# hawb-hat.net
KiCad netlist of a schematic drawn in EAGLE
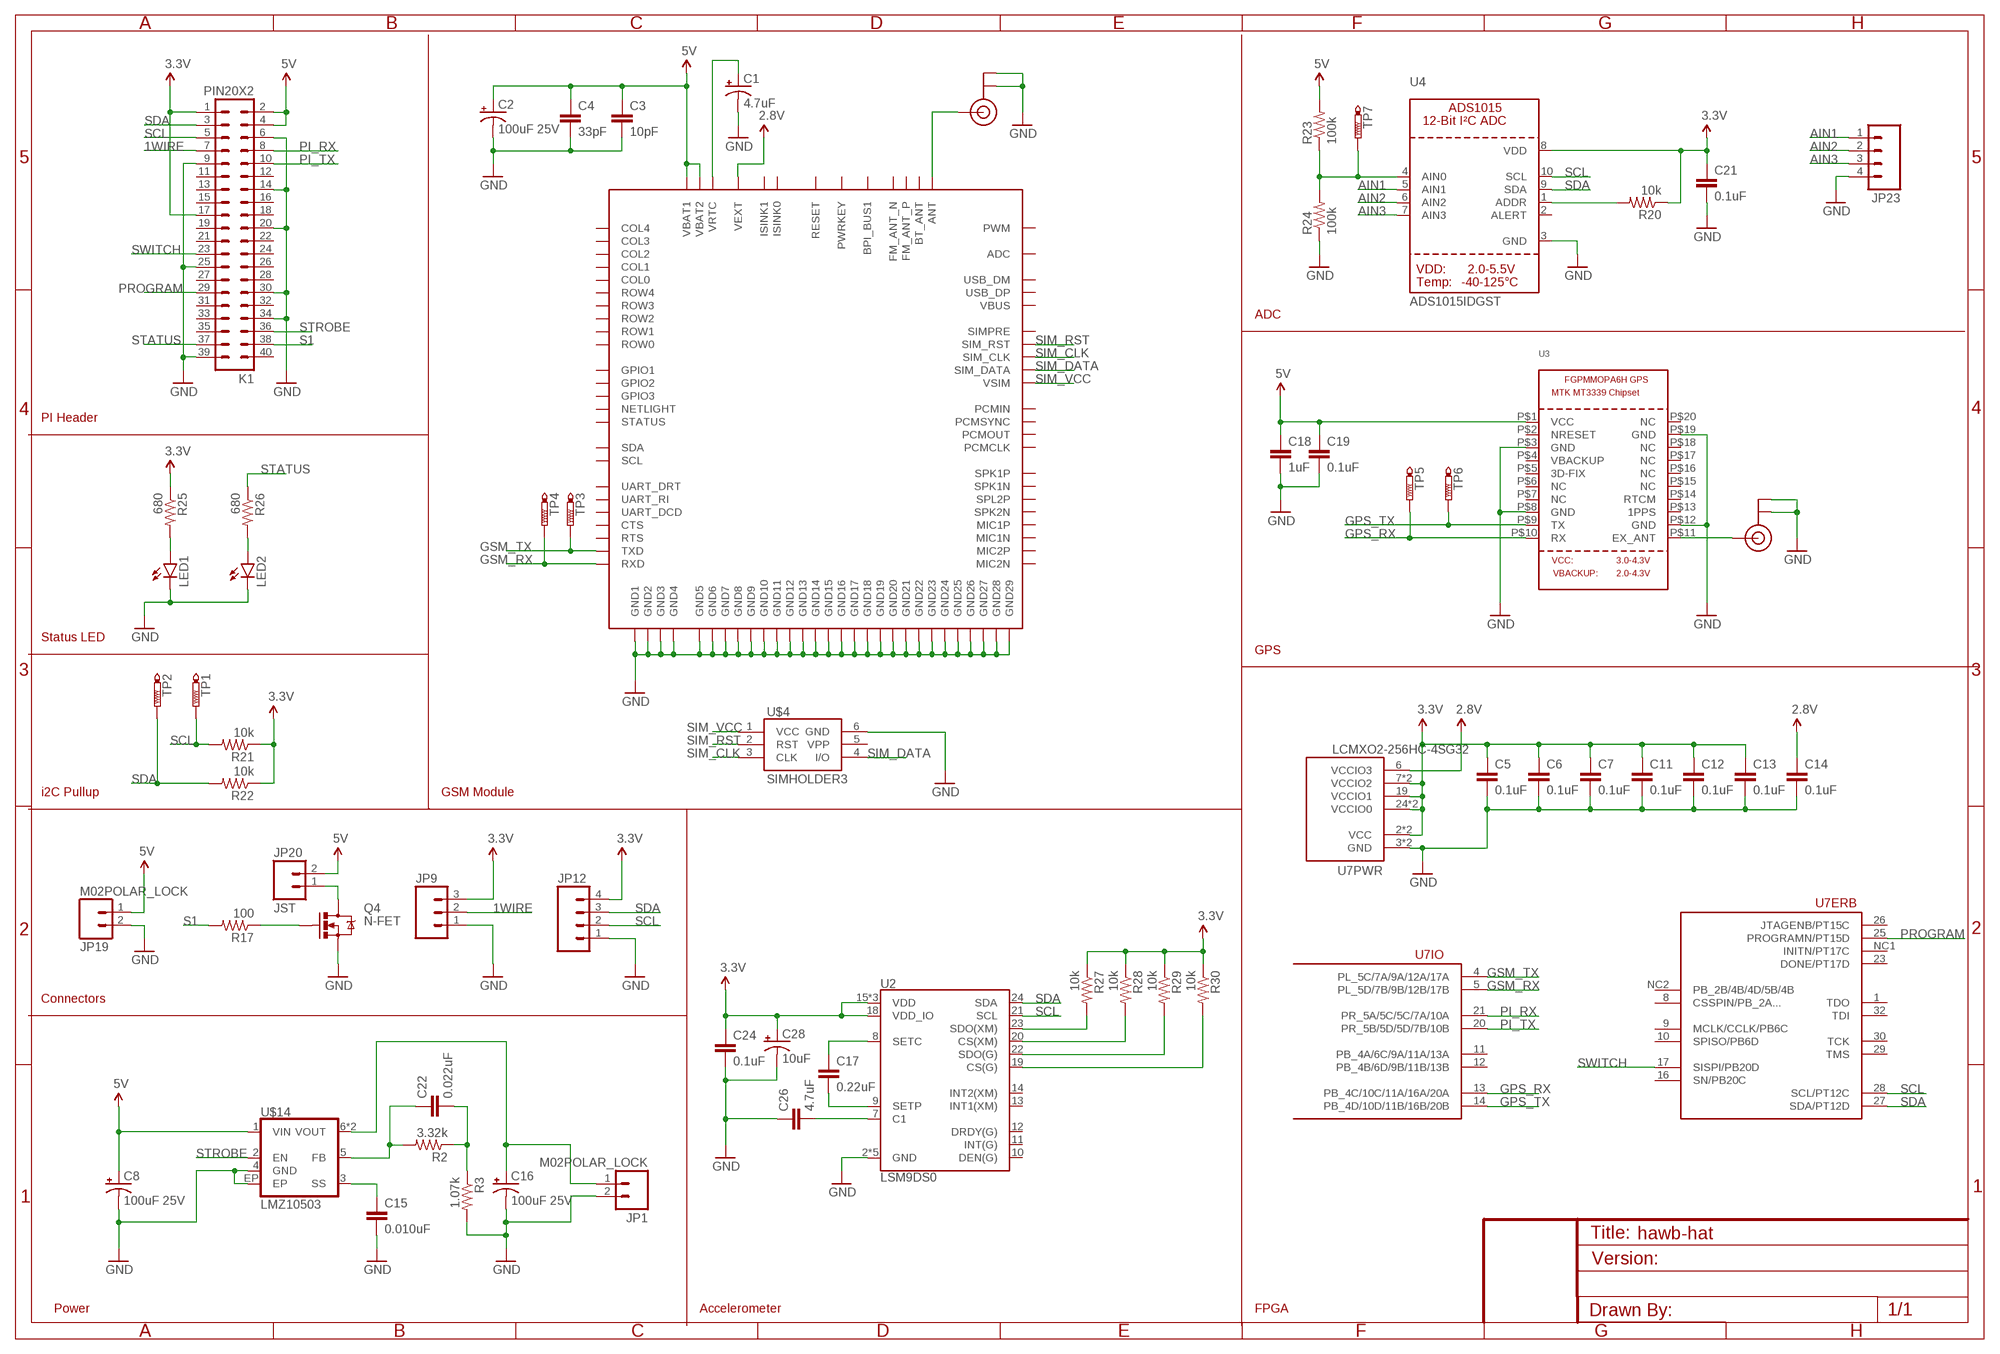
[diagram p0: schematic, sheet 1]

(export (version "E")
  (design (tool "Eeschema 10.0.6"))
  (components
    (comp (ref "C1")
      (value "4.7uF")
      (footprint "eagle-import:EIA3216-KIT")
      (libsource (lib "eagle-import") (part "sparkfun_CAP_POL1206-KIT"))
    )
    (comp (ref "C2")
      (value "100uF 25V")
      (footprint "eagle-import:NIPPON_F80")
      (libsource (lib "eagle-import") (part "CAP_POLF80"))
    )
    (comp (ref "C3")
      (value "10pF")
      (footprint "eagle-import:C0603")
      (libsource (lib "eagle-import") (part "C-EUC0603"))
    )
    (comp (ref "C4")
      (value "33pF")
      (footprint "eagle-import:C0603")
      (libsource (lib "eagle-import") (part "C-EUC0603"))
    )
    (comp (ref "C5")
      (value "0.1uF")
      (footprint "eagle-import:C0603")
      (libsource (lib "eagle-import") (part "C-EUC0603"))
    )
    (comp (ref "C6")
      (value "0.1uF")
      (footprint "eagle-import:C0603")
      (libsource (lib "eagle-import") (part "C-EUC0603"))
    )
    (comp (ref "C7")
      (value "0.1uF")
      (footprint "eagle-import:C0603")
      (libsource (lib "eagle-import") (part "C-EUC0603"))
    )
    (comp (ref "C8")
      (value "100uF 25V")
      (footprint "eagle-import:NIPPON_F80")
      (libsource (lib "eagle-import") (part "CAP_POLF80"))
    )
    (comp (ref "C11")
      (value "0.1uF")
      (footprint "eagle-import:C0603")
      (libsource (lib "eagle-import") (part "C-EUC0603"))
    )
    (comp (ref "C12")
      (value "0.1uF")
      (footprint "eagle-import:C0603")
      (libsource (lib "eagle-import") (part "C-EUC0603"))
    )
    (comp (ref "C13")
      (value "0.1uF")
      (footprint "eagle-import:C0603")
      (libsource (lib "eagle-import") (part "C-EUC0603"))
    )
    (comp (ref "C14")
      (value "0.1uF")
      (footprint "eagle-import:C0603")
      (libsource (lib "eagle-import") (part "C-EUC0603"))
    )
    (comp (ref "C15")
      (value "0.010uF")
      (footprint "eagle-import:C0603")
      (libsource (lib "eagle-import") (part "C-EUC0603"))
    )
    (comp (ref "C16")
      (value "100uF 25V")
      (footprint "eagle-import:NIPPON_F80")
      (libsource (lib "eagle-import") (part "CAP_POLF80"))
    )
    (comp (ref "C17")
      (value "0.22uF")
      (footprint "eagle-import:0603-CAP")
      (libsource (lib "eagle-import") (part "CAP0603-CAP"))
    )
    (comp (ref "C18")
      (value "1uF")
      (footprint "eagle-import:C0603")
      (libsource (lib "eagle-import") (part "C-EUC0603"))
    )
    (comp (ref "C19")
      (value "0.1uF")
      (footprint "eagle-import:C0603")
      (libsource (lib "eagle-import") (part "C-EUC0603"))
    )
    (comp (ref "C21")
      (value "0.1uF")
      (footprint "eagle-import:C0603")
      (libsource (lib "eagle-import") (part "C-EUC0603"))
    )
    (comp (ref "C22")
      (value "0.022uF")
      (footprint "eagle-import:C0603")
      (libsource (lib "eagle-import") (part "C-EUC0603"))
    )
    (comp (ref "C24")
      (value "0.1uF")
      (footprint "eagle-import:0603-CAP")
      (libsource (lib "eagle-import") (part "CAP0603-CAP"))
    )
    (comp (ref "C26")
      (value "4.7uF")
      (footprint "eagle-import:0603-CAP")
      (libsource (lib "eagle-import") (part "CAP0603-CAP"))
    )
    (comp (ref "C28")
      (value "10uF")
      (footprint "eagle-import:EIA3216")
      (libsource (lib "eagle-import") (part "sparkfun_CAP_POL1206"))
    )
    (comp (ref "JP1")
      (value "M02POLAR_LOCK")
      (footprint "eagle-import:MOLEX-1X2_LOCK")
      (libsource (lib "eagle-import") (part "M02POLAR_LOCK"))
    )
    (comp (ref "JP9")
      (value "M03JST-PTH-VERT")
      (footprint "eagle-import:JST-3-PTH-VERT")
      (libsource (lib "eagle-import") (part "M03JST-PTH-VERT"))
    )
    (comp (ref "JP12")
      (value "M04JST-PTH-VERT")
      (footprint "eagle-import:JST-4-PTH-VERT")
      (libsource (lib "eagle-import") (part "M04JST-PTH-VERT"))
    )
    (comp (ref "JP19")
      (value "M02POLAR_LOCK")
      (footprint "eagle-import:MOLEX-1X2_LOCK")
      (libsource (lib "eagle-import") (part "M02POLAR_LOCK"))
    )
    (comp (ref "JP20")
      (value "JST")
      (footprint "eagle-import:JST-2-PTH-VERT")
      (libsource (lib "eagle-import") (part "M02JST-PTH-VERT"))
    )
    (comp (ref "JP23")
      (value "M04JST-PTH-VERT")
      (footprint "eagle-import:JST-4-PTH-VERT")
      (libsource (lib "eagle-import") (part "M04JST-PTH-VERT"))
    )
    (comp (ref "K1")
      (value "PIN20X2")
      (footprint "eagle-import:PIN_20X2")
      (libsource (lib "eagle-import") (part "PIN20X2"))
    )
    (comp (ref "LED1")
      (value "LED1206")
      (footprint "eagle-import:LED-1206")
      (libsource (lib "eagle-import") (part "LED1206"))
    )
    (comp (ref "LED2")
      (value "LED1206")
      (footprint "eagle-import:LED-1206")
      (libsource (lib "eagle-import") (part "LED1206"))
    )
    (comp (ref "Q4")
      (value "N-FET")
      (footprint "eagle-import:SOT23-3")
      (libsource (lib "eagle-import") (part "MOSFET-NCHANNELSMD"))
    )
    (comp (ref "R2")
      (value "3.32k")
      (footprint "eagle-import:0603-RES")
      (libsource (lib "eagle-import") (part "RESISTOR0603-RES"))
    )
    (comp (ref "R3")
      (value "1.07k")
      (footprint "eagle-import:0603-RES")
      (libsource (lib "eagle-import") (part "RESISTOR0603-RES"))
    )
    (comp (ref "R17")
      (value "100")
      (footprint "eagle-import:0603-RES")
      (libsource (lib "eagle-import") (part "RESISTOR0603-RES"))
    )
    (comp (ref "R20")
      (value "10k")
      (footprint "eagle-import:0603-RES")
      (libsource (lib "eagle-import") (part "RESISTOR0603-RES"))
    )
    (comp (ref "R21")
      (value "10k")
      (footprint "eagle-import:0603-RES")
      (libsource (lib "eagle-import") (part "RESISTOR0603-RES"))
    )
    (comp (ref "R22")
      (value "10k")
      (footprint "eagle-import:0603-RES")
      (libsource (lib "eagle-import") (part "RESISTOR0603-RES"))
    )
    (comp (ref "R23")
      (value "100k")
      (footprint "eagle-import:0603-RES")
      (libsource (lib "eagle-import") (part "RESISTOR0603-RES"))
    )
    (comp (ref "R24")
      (value "100k")
      (footprint "eagle-import:0603-RES")
      (libsource (lib "eagle-import") (part "RESISTOR0603-RES"))
    )
    (comp (ref "R25")
      (value "680")
      (footprint "eagle-import:0603-RES")
      (libsource (lib "eagle-import") (part "RESISTOR0603-RES"))
    )
    (comp (ref "R26")
      (value "680")
      (footprint "eagle-import:0603-RES")
      (libsource (lib "eagle-import") (part "RESISTOR0603-RES"))
    )
    (comp (ref "R27")
      (value "10k")
      (footprint "eagle-import:0603-RES")
      (libsource (lib "eagle-import") (part "RESISTOR0603-RES"))
    )
    (comp (ref "R28")
      (value "10k")
      (footprint "eagle-import:0603-RES")
      (libsource (lib "eagle-import") (part "RESISTOR0603-RES"))
    )
    (comp (ref "R29")
      (value "10k")
      (footprint "eagle-import:0603-RES")
      (libsource (lib "eagle-import") (part "RESISTOR0603-RES"))
    )
    (comp (ref "R30")
      (value "10k")
      (footprint "eagle-import:0603-RES")
      (libsource (lib "eagle-import") (part "RESISTOR0603-RES"))
    )
    (comp (ref "TP1")
      (value "PTR1PAD1-13")
      (footprint "eagle-import:P1-13")
      (libsource (lib "eagle-import") (part "PTR1PAD1-13"))
    )
    (comp (ref "TP2")
      (value "PTR1PAD1-13")
      (footprint "eagle-import:P1-13")
      (libsource (lib "eagle-import") (part "PTR1PAD1-13"))
    )
    (comp (ref "TP3")
      (value "PTR1PAD1-13")
      (footprint "eagle-import:P1-13")
      (libsource (lib "eagle-import") (part "PTR1PAD1-13"))
    )
    (comp (ref "TP4")
      (value "PTR1PAD1-13")
      (footprint "eagle-import:P1-13")
      (libsource (lib "eagle-import") (part "PTR1PAD1-13"))
    )
    (comp (ref "TP5")
      (value "PTR1PAD1-13")
      (footprint "eagle-import:P1-13")
      (libsource (lib "eagle-import") (part "PTR1PAD1-13"))
    )
    (comp (ref "TP6")
      (value "PTR1PAD1-13")
      (footprint "eagle-import:P1-13")
      (libsource (lib "eagle-import") (part "PTR1PAD1-13"))
    )
    (comp (ref "TP7")
      (value "PTR1PAD1-13")
      (footprint "eagle-import:P1-13")
      (libsource (lib "eagle-import") (part "PTR1PAD1-13"))
    )
    (comp (ref "U$1")
      (value "U.FL")
      (footprint "eagle-import:U.FL")
      (libsource (lib "eagle-import") (part "U.FL"))
    )
    (comp (ref "U$2")
      (value "U.FL")
      (footprint "eagle-import:U.FL")
      (libsource (lib "eagle-import") (part "U.FL"))
    )
    (comp (ref "U$4")
      (value "SIMHOLDER3")
      (footprint "eagle-import:SIMHOLDER3")
      (libsource (lib "eagle-import") (part "SIMHOLDER3"))
    )
    (comp (ref "U$5")
      (value "SIM800H")
      (footprint "eagle-import:SIM800")
      (libsource (lib "eagle-import") (part "SIM800H"))
    )
    (comp (ref "U$14")
      (value "LMZ10503")
      (footprint "eagle-import:TO-PMOD-7")
      (libsource (lib "eagle-import") (part "LMZ10503"))
    )
    (comp (ref "U2")
      (value "LSM9DS0")
      (footprint "eagle-import:LGA-24")
      (libsource (lib "eagle-import") (part "LSM9DS0"))
    )
    (comp (ref "U3")
      (value "GPS_FGPMMOPA6H")
      (footprint "eagle-import:FGPMMOPA6H")
      (libsource (lib "eagle-import") (part "GPS_FGPMMOPA6H"))
    )
    (comp (ref "U4")
      (value "ADS1015IDGST")
      (footprint "eagle-import:MSOP10")
      (libsource (lib "eagle-import") (part "ADC_ADS1015"))
    )
    (comp (ref "U7")
      (value "LCMXO2-256HC-4SG32")
      (footprint "eagle-import:QFN-32")
      (libsource (lib "eagle-import") (part "LCMXO2-256SG32HC-4"))
    )
  )
  (nets
    (net (code "1") (name "/1WIRE") (class "Default")
      (node (ref "JP9") (pin "2") (pinfunction "2_2") (pintype "passive"))
      (node (ref "K1") (pin "7") (pinfunction "7_7") (pintype "passive"))
    )
    (net (code "2") (name "/AIN1") (class "Default")
      (node (ref "JP23") (pin "1") (pinfunction "1_1") (pintype "passive"))
      (node (ref "U4") (pin "5") (pinfunction "AIN1_5") (pintype "bidirectional"))
    )
    (net (code "3") (name "/AIN2") (class "Default")
      (node (ref "JP23") (pin "2") (pinfunction "2_2") (pintype "passive"))
      (node (ref "U4") (pin "6") (pinfunction "AIN2_6") (pintype "bidirectional"))
    )
    (net (code "4") (name "/AIN3") (class "Default")
      (node (ref "JP23") (pin "3") (pinfunction "3_3") (pintype "passive"))
      (node (ref "U4") (pin "7") (pinfunction "AIN3_7") (pintype "bidirectional"))
    )
    (net (code "5") (name "/GPS_RX") (class "Default")
      (node (ref "TP5") (pin "TP") (pinfunction "TP_TP") (pintype "input"))
      (node (ref "U3") (pin "P$10") (pinfunction "RX_P$10") (pintype "bidirectional"))
      (node (ref "U7") (pin "13") (pinfunction "PB_4C/10C/11A/16A/20A_13") (pintype "bidirectional"))
    )
    (net (code "6") (name "/GPS_TX") (class "Default")
      (node (ref "TP6") (pin "TP") (pinfunction "TP_TP") (pintype "input"))
      (node (ref "U3") (pin "P$9") (pinfunction "TX_P$9") (pintype "bidirectional"))
      (node (ref "U7") (pin "14") (pinfunction "PB_4D/10D/11B/16B/20B_14") (pintype "bidirectional"))
    )
    (net (code "7") (name "/GSM_RX") (class "Default")
      (node (ref "TP4") (pin "TP") (pinfunction "TP_TP") (pintype "input"))
      (node (ref "U$5") (pin "P$31") (pinfunction "RXD_P$31") (pintype "bidirectional"))
      (node (ref "U7") (pin "5") (pinfunction "PL_5D/7B/9B/12B/17B_5") (pintype "bidirectional"))
    )
    (net (code "8") (name "/GSM_TX") (class "Default")
      (node (ref "TP3") (pin "TP") (pinfunction "TP_TP") (pintype "input"))
      (node (ref "U$5") (pin "P$32") (pinfunction "TXD_P$32") (pintype "bidirectional"))
      (node (ref "U7") (pin "4") (pinfunction "PL_5C/7A/9A/12A/17A_4") (pintype "bidirectional"))
    )
    (net (code "9") (name "/PI_RX") (class "Default")
      (node (ref "K1") (pin "8") (pinfunction "8_8") (pintype "passive"))
      (node (ref "U7") (pin "21") (pinfunction "PR_5A/5C/5C/7A/10A_21") (pintype "bidirectional"))
    )
    (net (code "10") (name "/PI_TX") (class "Default")
      (node (ref "K1") (pin "10") (pinfunction "10_10") (pintype "passive"))
      (node (ref "U7") (pin "20") (pinfunction "PR_5B/5D/5D/7B/10B_20") (pintype "bidirectional"))
    )
    (net (code "11") (name "/PROGRAM") (class "Default")
      (node (ref "K1") (pin "29") (pinfunction "29_29") (pintype "passive"))
      (node (ref "U7") (pin "25") (pinfunction "PROGRAMN/PT15D_25") (pintype "bidirectional"))
    )
    (net (code "12") (name "/S1") (class "Default")
      (node (ref "K1") (pin "38") (pinfunction "38_38") (pintype "passive"))
      (node (ref "R17") (pin "2") (pinfunction "2_2") (pintype "passive"))
    )
    (net (code "13") (name "/SCL") (class "Default")
      (node (ref "JP12") (pin "2") (pinfunction "2_2") (pintype "passive"))
      (node (ref "K1") (pin "5") (pinfunction "5_5") (pintype "passive"))
      (node (ref "R21") (pin "2") (pinfunction "2_2") (pintype "passive"))
      (node (ref "TP1") (pin "TP") (pinfunction "TP_TP") (pintype "input"))
      (node (ref "U2") (pin "21") (pinfunction "SCL_21") (pintype "bidirectional"))
      (node (ref "U4") (pin "10") (pinfunction "SCL_10") (pintype "bidirectional"))
      (node (ref "U7") (pin "28") (pinfunction "SCL/PT12C_28") (pintype "bidirectional"))
    )
    (net (code "14") (name "/SDA") (class "Default")
      (node (ref "JP12") (pin "3") (pinfunction "3_3") (pintype "passive"))
      (node (ref "K1") (pin "3") (pinfunction "3_3") (pintype "passive"))
      (node (ref "R22") (pin "2") (pinfunction "2_2") (pintype "passive"))
      (node (ref "TP2") (pin "TP") (pinfunction "TP_TP") (pintype "input"))
      (node (ref "U2") (pin "24") (pinfunction "SDA_24") (pintype "bidirectional"))
      (node (ref "U4") (pin "9") (pinfunction "SDA_9") (pintype "bidirectional"))
      (node (ref "U7") (pin "27") (pinfunction "SDA/PT12D_27") (pintype "bidirectional"))
    )
    (net (code "15") (name "/SIM_CLK") (class "Default")
      (node (ref "U$4") (pin "3") (pinfunction "CLK_3") (pintype "bidirectional"))
      (node (ref "U$5") (pin "P$55") (pinfunction "SIM_CLK_P$55") (pintype "bidirectional"))
    )
    (net (code "16") (name "/SIM_DATA") (class "Default")
      (node (ref "U$4") (pin "4") (pinfunction "I/O_4") (pintype "bidirectional"))
      (node (ref "U$5") (pin "P$14") (pinfunction "SIM_DATA_P$14") (pintype "bidirectional"))
    )
    (net (code "17") (name "/SIM_RST") (class "Default")
      (node (ref "U$4") (pin "2") (pinfunction "RST_2") (pintype "bidirectional"))
      (node (ref "U$5") (pin "P$15") (pinfunction "SIM_RST_P$15") (pintype "bidirectional"))
    )
    (net (code "18") (name "/SIM_VCC") (class "Default")
      (node (ref "U$4") (pin "1") (pinfunction "VCC_1") (pintype "bidirectional"))
      (node (ref "U$5") (pin "P$16") (pinfunction "VSIM_P$16") (pintype "bidirectional"))
    )
    (net (code "19") (name "/STATUS") (class "Default")
      (node (ref "K1") (pin "37") (pinfunction "37_37") (pintype "passive"))
      (node (ref "R26") (pin "1") (pinfunction "1_1") (pintype "passive"))
    )
    (net (code "20") (name "/STROBE") (class "Default")
      (node (ref "K1") (pin "36") (pinfunction "36_36") (pintype "passive"))
      (node (ref "U$14") (pin "2") (pinfunction "EN_2") (pintype "bidirectional"))
    )
    (net (code "21") (name "/SWITCH") (class "Default")
      (node (ref "K1") (pin "23") (pinfunction "23_23") (pintype "passive"))
      (node (ref "U7") (pin "17") (pinfunction "SISPI/PB20D_17") (pintype "bidirectional"))
    )
    (net (code "22") (name "2.8V") (class "Default")
      (node (ref "C14") (pin "1") (pinfunction "1_1") (pintype "passive"))
      (node (ref "U$5") (pin "P$18") (pinfunction "VEXT_P$18") (pintype "bidirectional"))
      (node (ref "U7") (pin "6") (pinfunction "VCCIO3_6") (pintype "bidirectional"))
    )
    (net (code "23") (name "3.3V") (class "Default")
      (node (ref "C11") (pin "1") (pinfunction "1_1") (pintype "passive"))
      (node (ref "C12") (pin "1") (pinfunction "1_1") (pintype "passive"))
      (node (ref "C13") (pin "1") (pinfunction "1_1") (pintype "passive"))
      (node (ref "C21") (pin "1") (pinfunction "1_1") (pintype "passive"))
      (node (ref "C24") (pin "1") (pinfunction "1_1") (pintype "passive"))
      (node (ref "C28") (pin "A") (pinfunction "+_A") (pintype "passive"))
      (node (ref "C5") (pin "1") (pinfunction "1_1") (pintype "passive"))
      (node (ref "C6") (pin "1") (pinfunction "1_1") (pintype "passive"))
      (node (ref "C7") (pin "1") (pinfunction "1_1") (pintype "passive"))
      (node (ref "JP12") (pin "4") (pinfunction "4_4") (pintype "passive"))
      (node (ref "JP9") (pin "3") (pinfunction "3_3") (pintype "passive"))
      (node (ref "K1") (pin "1") (pinfunction "1_1") (pintype "passive"))
      (node (ref "K1") (pin "17") (pinfunction "17_17") (pintype "passive"))
      (node (ref "R20") (pin "1") (pinfunction "1_1") (pintype "passive"))
      (node (ref "R21") (pin "1") (pinfunction "1_1") (pintype "passive"))
      (node (ref "R22") (pin "1") (pinfunction "1_1") (pintype "passive"))
      (node (ref "R25") (pin "1") (pinfunction "1_1") (pintype "passive"))
      (node (ref "R27") (pin "1") (pinfunction "1_1") (pintype "passive"))
      (node (ref "R28") (pin "1") (pinfunction "1_1") (pintype "passive"))
      (node (ref "R29") (pin "1") (pinfunction "1_1") (pintype "passive"))
      (node (ref "R30") (pin "1") (pinfunction "1_1") (pintype "passive"))
      (node (ref "U2") (pin "15") (pinfunction "VDD_15") (pintype "bidirectional"))
      (node (ref "U2") (pin "16") (pinfunction "VDD_16") (pintype "bidirectional"))
      (node (ref "U2") (pin "17") (pinfunction "VDD_17") (pintype "bidirectional"))
      (node (ref "U2") (pin "18") (pinfunction "VDD_IO_18") (pintype "bidirectional"))
      (node (ref "U4") (pin "8") (pinfunction "VDD_8") (pintype "bidirectional"))
      (node (ref "U7") (pin "15") (pinfunction "VCCIO2_15") (pintype "bidirectional"))
      (node (ref "U7") (pin "18") (pinfunction "VCC_18") (pintype "bidirectional"))
      (node (ref "U7") (pin "19") (pinfunction "VCCIO1_19") (pintype "bidirectional"))
      (node (ref "U7") (pin "2") (pinfunction "VCC_2") (pintype "bidirectional"))
      (node (ref "U7") (pin "24") (pinfunction "VCCIO0_24") (pintype "bidirectional"))
      (node (ref "U7") (pin "31") (pinfunction "VCCIO0_31") (pintype "bidirectional"))
      (node (ref "U7") (pin "7") (pinfunction "VCCIO2_7") (pintype "bidirectional"))
    )
    (net (code "24") (name "5V") (class "Default")
      (node (ref "C18") (pin "1") (pinfunction "1_1") (pintype "passive"))
      (node (ref "C19") (pin "1") (pinfunction "1_1") (pintype "passive"))
      (node (ref "C2") (pin "+") (pinfunction "+_+") (pintype "passive"))
      (node (ref "C3") (pin "1") (pinfunction "1_1") (pintype "passive"))
      (node (ref "C4") (pin "1") (pinfunction "1_1") (pintype "passive"))
      (node (ref "C8") (pin "+") (pinfunction "+_+") (pintype "passive"))
      (node (ref "JP19") (pin "1") (pinfunction "1_1") (pintype "passive"))
      (node (ref "JP20") (pin "2") (pinfunction "2_2") (pintype "passive"))
      (node (ref "K1") (pin "2") (pinfunction "2_2") (pintype "passive"))
      (node (ref "K1") (pin "4") (pinfunction "4_4") (pintype "passive"))
      (node (ref "R23") (pin "2") (pinfunction "2_2") (pintype "passive"))
      (node (ref "U$14") (pin "1") (pinfunction "VIN_1") (pintype "bidirectional"))
      (node (ref "U$5") (pin "P$1") (pinfunction "VBAT1_P$1") (pintype "bidirectional"))
      (node (ref "U$5") (pin "P$42") (pinfunction "VBAT2_P$42") (pintype "bidirectional"))
      (node (ref "U3") (pin "P$1") (pinfunction "VCC_P$1") (pintype "bidirectional"))
    )
    (net (code "25") (name "GND") (class "Default")
      (node (ref "C1") (pin "C") (pinfunction "-_C") (pintype "passive"))
      (node (ref "C11") (pin "2") (pinfunction "2_2") (pintype "passive"))
      (node (ref "C12") (pin "2") (pinfunction "2_2") (pintype "passive"))
      (node (ref "C13") (pin "2") (pinfunction "2_2") (pintype "passive"))
      (node (ref "C14") (pin "2") (pinfunction "2_2") (pintype "passive"))
      (node (ref "C15") (pin "2") (pinfunction "2_2") (pintype "passive"))
      (node (ref "C16") (pin "-") (pinfunction "-_-") (pintype "passive"))
      (node (ref "C18") (pin "2") (pinfunction "2_2") (pintype "passive"))
      (node (ref "C19") (pin "2") (pinfunction "2_2") (pintype "passive"))
      (node (ref "C2") (pin "-") (pinfunction "-_-") (pintype "passive"))
      (node (ref "C21") (pin "2") (pinfunction "2_2") (pintype "passive"))
      (node (ref "C24") (pin "2") (pinfunction "2_2") (pintype "passive"))
      (node (ref "C26") (pin "1") (pinfunction "1_1") (pintype "passive"))
      (node (ref "C28") (pin "C") (pinfunction "-_C") (pintype "passive"))
      (node (ref "C3") (pin "2") (pinfunction "2_2") (pintype "passive"))
      (node (ref "C4") (pin "2") (pinfunction "2_2") (pintype "passive"))
      (node (ref "C5") (pin "2") (pinfunction "2_2") (pintype "passive"))
      (node (ref "C6") (pin "2") (pinfunction "2_2") (pintype "passive"))
      (node (ref "C7") (pin "2") (pinfunction "2_2") (pintype "passive"))
      (node (ref "C8") (pin "-") (pinfunction "-_-") (pintype "passive"))
      (node (ref "JP1") (pin "2") (pinfunction "2_2") (pintype "passive"))
      (node (ref "JP12") (pin "1") (pinfunction "1_1") (pintype "passive"))
      (node (ref "JP19") (pin "2") (pinfunction "2_2") (pintype "passive"))
      (node (ref "JP23") (pin "4") (pinfunction "4_4") (pintype "passive"))
      (node (ref "JP9") (pin "1") (pinfunction "1_1") (pintype "passive"))
      (node (ref "K1") (pin "14") (pinfunction "14_14") (pintype "passive"))
      (node (ref "K1") (pin "20") (pinfunction "20_20") (pintype "passive"))
      (node (ref "K1") (pin "25") (pinfunction "25_25") (pintype "passive"))
      (node (ref "K1") (pin "30") (pinfunction "30_30") (pintype "passive"))
      (node (ref "K1") (pin "34") (pinfunction "34_34") (pintype "passive"))
      (node (ref "K1") (pin "39") (pinfunction "39_39") (pintype "passive"))
      (node (ref "K1") (pin "6") (pinfunction "6_6") (pintype "passive"))
      (node (ref "K1") (pin "9") (pinfunction "9_9") (pintype "passive"))
      (node (ref "LED1") (pin "C") (pinfunction "C_C") (pintype "passive"))
      (node (ref "LED2") (pin "C") (pinfunction "C_C") (pintype "passive"))
      (node (ref "Q4") (pin "2") (pinfunction "S_2") (pintype "passive"))
      (node (ref "R24") (pin "1") (pinfunction "1_1") (pintype "passive"))
      (node (ref "R3") (pin "2") (pinfunction "2_2") (pintype "passive"))
      (node (ref "U$1") (pin "P$1") (pinfunction "GND_P$1") (pintype "bidirectional"))
      (node (ref "U$1") (pin "P$2") (pinfunction "GND_P$2") (pintype "bidirectional"))
      (node (ref "U$14") (pin "4") (pinfunction "GND_4") (pintype "bidirectional"))
      (node (ref "U$14") (pin "EP") (pinfunction "EP_EP") (pintype "bidirectional"))
      (node (ref "U$2") (pin "P$1") (pinfunction "GND_P$1") (pintype "bidirectional"))
      (node (ref "U$2") (pin "P$2") (pinfunction "GND_P$2") (pintype "bidirectional"))
      (node (ref "U$4") (pin "6") (pinfunction "GND_6") (pintype "bidirectional"))
      (node (ref "U$5") (pin "P$2") (pinfunction "GND1_P$2") (pintype "bidirectional"))
      (node (ref "U$5") (pin "P$35") (pinfunction "GND5_P$35") (pintype "bidirectional"))
      (node (ref "U$5") (pin "P$37") (pinfunction "GND6_P$37") (pintype "bidirectional"))
      (node (ref "U$5") (pin "P$38") (pinfunction "GND7_P$38") (pintype "bidirectional"))
      (node (ref "U$5") (pin "P$39") (pinfunction "GND8_P$39") (pintype "bidirectional"))
      (node (ref "U$5") (pin "P$41") (pinfunction "GND12_P$41") (pintype "bidirectional"))
      (node (ref "U$5") (pin "P$43") (pinfunction "GND2_P$43") (pintype "bidirectional"))
      (node (ref "U$5") (pin "P$44") (pinfunction "GND3_P$44") (pintype "bidirectional"))
      (node (ref "U$5") (pin "P$45") (pinfunction "GND4_P$45") (pintype "bidirectional"))
      (node (ref "U$5") (pin "P$58") (pinfunction "GND9_P$58") (pintype "bidirectional"))
      (node (ref "U$5") (pin "P$6") (pinfunction "GND10_P$6") (pintype "bidirectional"))
      (node (ref "U$5") (pin "P$67") (pinfunction "GND13_P$67") (pintype "bidirectional"))
      (node (ref "U$5") (pin "P$71") (pinfunction "GND14_P$71") (pintype "bidirectional"))
      (node (ref "U$5") (pin "P$72") (pinfunction "GND15_P$72") (pintype "bidirectional"))
      (node (ref "U$5") (pin "P$73") (pinfunction "GND16_P$73") (pintype "bidirectional"))
      (node (ref "U$5") (pin "P$76") (pinfunction "GND17_P$76") (pintype "bidirectional"))
      (node (ref "U$5") (pin "P$77") (pinfunction "GND18_P$77") (pintype "bidirectional"))
      (node (ref "U$5") (pin "P$78") (pinfunction "GND19_P$78") (pintype "bidirectional"))
      (node (ref "U$5") (pin "P$79") (pinfunction "GND20_P$79") (pintype "bidirectional"))
      (node (ref "U$5") (pin "P$8") (pinfunction "GND11_P$8") (pintype "bidirectional"))
      (node (ref "U$5") (pin "P$80") (pinfunction "GND21_P$80") (pintype "bidirectional"))
      (node (ref "U$5") (pin "P$81") (pinfunction "GND22_P$81") (pintype "bidirectional"))
      (node (ref "U$5") (pin "P$82") (pinfunction "GND23_P$82") (pintype "bidirectional"))
      (node (ref "U$5") (pin "P$83") (pinfunction "GND24_P$83") (pintype "bidirectional"))
      (node (ref "U$5") (pin "P$84") (pinfunction "GND25_P$84") (pintype "bidirectional"))
      (node (ref "U$5") (pin "P$85") (pinfunction "GND26_P$85") (pintype "bidirectional"))
      (node (ref "U$5") (pin "P$86") (pinfunction "GND27_P$86") (pintype "bidirectional"))
      (node (ref "U$5") (pin "P$87") (pinfunction "GND28_P$87") (pintype "bidirectional"))
      (node (ref "U$5") (pin "P$88") (pinfunction "GND29_P$88") (pintype "bidirectional"))
      (node (ref "U2") (pin "2") (pinfunction "GND_2") (pintype "bidirectional"))
      (node (ref "U2") (pin "3") (pinfunction "GND_3") (pintype "bidirectional"))
      (node (ref "U2") (pin "4") (pinfunction "GND_4") (pintype "bidirectional"))
      (node (ref "U2") (pin "5") (pinfunction "GND_5") (pintype "bidirectional"))
      (node (ref "U2") (pin "6") (pinfunction "GND_6") (pintype "bidirectional"))
      (node (ref "U3") (pin "P$12") (pinfunction "GND_P$12") (pintype "bidirectional"))
      (node (ref "U3") (pin "P$19") (pinfunction "GND_P$19") (pintype "bidirectional"))
      (node (ref "U3") (pin "P$3") (pinfunction "GND_P$3") (pintype "bidirectional"))
      (node (ref "U3") (pin "P$8") (pinfunction "GND_P$8") (pintype "bidirectional"))
      (node (ref "U4") (pin "3") (pinfunction "GND_3") (pintype "bidirectional"))
      (node (ref "U7") (pin "22") (pinfunction "GND_22") (pintype "bidirectional"))
      (node (ref "U7") (pin "3") (pinfunction "GND_3") (pintype "bidirectional"))
    )
    (net (code "26") (name "Net-(C1-+)") (class "Default")
      (node (ref "C1") (pin "A") (pinfunction "+_A") (pintype "passive"))
      (node (ref "U$5") (pin "P$56") (pinfunction "VRTC_P$56") (pintype "bidirectional"))
    )
    (net (code "27") (name "Net-(C16-Pad+)") (class "Default")
      (node (ref "C16") (pin "+") (pinfunction "+_+") (pintype "passive"))
      (node (ref "JP1") (pin "1") (pinfunction "1_1") (pintype "passive"))
      (node (ref "U$14") (pin "6") (pinfunction "VOUT_6") (pintype "bidirectional"))
      (node (ref "U$14") (pin "7") (pinfunction "VOUT_7") (pintype "bidirectional"))
    )
    (net (code "28") (name "Net-(C22-Pad2)") (class "Default")
      (node (ref "C22") (pin "2") (pinfunction "2_2") (pintype "passive"))
      (node (ref "R2") (pin "1") (pinfunction "1_1") (pintype "passive"))
      (node (ref "R3") (pin "1") (pinfunction "1_1") (pintype "passive"))
    )
    (net (code "29") (name "Net-(LED1-PadA)") (class "Default")
      (node (ref "LED1") (pin "A") (pinfunction "A_A") (pintype "passive"))
      (node (ref "R25") (pin "2") (pinfunction "2_2") (pintype "passive"))
    )
    (net (code "30") (name "Net-(LED2-PadA)") (class "Default")
      (node (ref "LED2") (pin "A") (pinfunction "A_A") (pintype "passive"))
      (node (ref "R26") (pin "2") (pinfunction "2_2") (pintype "passive"))
    )
    (net (code "31") (name "Net-(Q4-D)") (class "Default")
      (node (ref "JP20") (pin "1") (pinfunction "1_1") (pintype "passive"))
      (node (ref "Q4") (pin "3") (pinfunction "D_3") (pintype "passive"))
    )
    (net (code "32") (name "Net-(Q4-G)") (class "Default")
      (node (ref "Q4") (pin "1") (pinfunction "G_1") (pintype "passive"))
      (node (ref "R17") (pin "1") (pinfunction "1_1") (pintype "passive"))
    )
    (net (code "33") (name "Net-(U$1-SIGNAL)") (class "Default")
      (node (ref "U$1") (pin "P$3") (pinfunction "SIGNAL_P$3") (pintype "bidirectional"))
      (node (ref "U$5") (pin "P$40") (pinfunction "ANT_P$40") (pintype "bidirectional"))
    )
    (net (code "34") (name "Net-(U$2-SIGNAL)") (class "Default")
      (node (ref "U$2") (pin "P$3") (pinfunction "SIGNAL_P$3") (pintype "bidirectional"))
      (node (ref "U3") (pin "P$11") (pinfunction "EX_ANT_P$11") (pintype "bidirectional"))
    )
    (net (code "35") (name "Net-(U$14-FB)") (class "Default")
      (node (ref "C22") (pin "1") (pinfunction "1_1") (pintype "passive"))
      (node (ref "R2") (pin "2") (pinfunction "2_2") (pintype "passive"))
      (node (ref "U$14") (pin "5") (pinfunction "FB_5") (pintype "bidirectional"))
    )
    (net (code "36") (name "Net-(U$14-SS)") (class "Default")
      (node (ref "C15") (pin "1") (pinfunction "1_1") (pintype "passive"))
      (node (ref "U$14") (pin "3") (pinfunction "SS_3") (pintype "bidirectional"))
    )
    (net (code "37") (name "Net-(U2-C1)") (class "Default")
      (node (ref "C26") (pin "2") (pinfunction "2_2") (pintype "passive"))
      (node (ref "U2") (pin "7") (pinfunction "C1_7") (pintype "bidirectional"))
    )
    (net (code "38") (name "Net-(U2-CS(G))") (class "Default")
      (node (ref "R30") (pin "2") (pinfunction "2_2") (pintype "passive"))
      (node (ref "U2") (pin "19") (pinfunction "CS(G)_19") (pintype "bidirectional"))
    )
    (net (code "39") (name "Net-(U2-CS(XM))") (class "Default")
      (node (ref "R28") (pin "2") (pinfunction "2_2") (pintype "passive"))
      (node (ref "U2") (pin "20") (pinfunction "CS(XM)_20") (pintype "bidirectional"))
    )
    (net (code "40") (name "Net-(U2-SDO(G))") (class "Default")
      (node (ref "R29") (pin "2") (pinfunction "2_2") (pintype "passive"))
      (node (ref "U2") (pin "22") (pinfunction "SDO(G)_22") (pintype "bidirectional"))
    )
    (net (code "41") (name "Net-(U2-SDO(XM))") (class "Default")
      (node (ref "R27") (pin "2") (pinfunction "2_2") (pintype "passive"))
      (node (ref "U2") (pin "23") (pinfunction "SDO(XM)_23") (pintype "bidirectional"))
    )
    (net (code "42") (name "Net-(U2-SETC)") (class "Default")
      (node (ref "C17") (pin "1") (pinfunction "1_1") (pintype "passive"))
      (node (ref "U2") (pin "8") (pinfunction "SETC_8") (pintype "bidirectional"))
    )
    (net (code "43") (name "Net-(U2-SETP)") (class "Default")
      (node (ref "C17") (pin "2") (pinfunction "2_2") (pintype "passive"))
      (node (ref "U2") (pin "9") (pinfunction "SETP_9") (pintype "bidirectional"))
    )
    (net (code "44") (name "Net-(U4-ADDR)") (class "Default")
      (node (ref "R20") (pin "2") (pinfunction "2_2") (pintype "passive"))
      (node (ref "U4") (pin "1") (pinfunction "ADDR_1") (pintype "bidirectional"))
    )
    (net (code "45") (name "Net-(U4-AIN0)") (class "Default")
      (node (ref "R23") (pin "1") (pinfunction "1_1") (pintype "passive"))
      (node (ref "R24") (pin "2") (pinfunction "2_2") (pintype "passive"))
      (node (ref "TP7") (pin "TP") (pinfunction "TP_TP") (pintype "input"))
      (node (ref "U4") (pin "4") (pinfunction "AIN0_4") (pintype "bidirectional"))
    )
    (net (code "46") (name "unconnected-(K1-Pad11)") (class "Default")
      (node (ref "K1") (pin "11") (pinfunction "11_11") (pintype "passive"))
    )
    (net (code "47") (name "unconnected-(K1-Pad12)") (class "Default")
      (node (ref "K1") (pin "12") (pinfunction "12_12") (pintype "passive"))
    )
    (net (code "48") (name "unconnected-(K1-Pad13)") (class "Default")
      (node (ref "K1") (pin "13") (pinfunction "13_13") (pintype "passive"))
    )
    (net (code "49") (name "unconnected-(K1-Pad15)") (class "Default")
      (node (ref "K1") (pin "15") (pinfunction "15_15") (pintype "passive"))
    )
    (net (code "50") (name "unconnected-(K1-Pad16)") (class "Default")
      (node (ref "K1") (pin "16") (pinfunction "16_16") (pintype "passive"))
    )
    (net (code "51") (name "unconnected-(K1-Pad18)") (class "Default")
      (node (ref "K1") (pin "18") (pinfunction "18_18") (pintype "passive"))
    )
    (net (code "52") (name "unconnected-(K1-Pad19)") (class "Default")
      (node (ref "K1") (pin "19") (pinfunction "19_19") (pintype "passive"))
    )
    (net (code "53") (name "unconnected-(K1-Pad21)") (class "Default")
      (node (ref "K1") (pin "21") (pinfunction "21_21") (pintype "passive"))
    )
    (net (code "54") (name "unconnected-(K1-Pad22)") (class "Default")
      (node (ref "K1") (pin "22") (pinfunction "22_22") (pintype "passive"))
    )
    (net (code "55") (name "unconnected-(K1-Pad24)") (class "Default")
      (node (ref "K1") (pin "24") (pinfunction "24_24") (pintype "passive"))
    )
    (net (code "56") (name "unconnected-(K1-Pad26)") (class "Default")
      (node (ref "K1") (pin "26") (pinfunction "26_26") (pintype "passive"))
    )
    (net (code "57") (name "unconnected-(K1-Pad27)") (class "Default")
      (node (ref "K1") (pin "27") (pinfunction "27_27") (pintype "passive"))
    )
    (net (code "58") (name "unconnected-(K1-Pad28)") (class "Default")
      (node (ref "K1") (pin "28") (pinfunction "28_28") (pintype "passive"))
    )
    (net (code "59") (name "unconnected-(K1-Pad31)") (class "Default")
      (node (ref "K1") (pin "31") (pinfunction "31_31") (pintype "passive"))
    )
    (net (code "60") (name "unconnected-(K1-Pad32)") (class "Default")
      (node (ref "K1") (pin "32") (pinfunction "32_32") (pintype "passive"))
    )
    (net (code "61") (name "unconnected-(K1-Pad33)") (class "Default")
      (node (ref "K1") (pin "33") (pinfunction "33_33") (pintype "passive"))
    )
    (net (code "62") (name "unconnected-(K1-Pad35)") (class "Default")
      (node (ref "K1") (pin "35") (pinfunction "35_35") (pintype "passive"))
    )
    (net (code "63") (name "unconnected-(K1-Pad40)") (class "Default")
      (node (ref "K1") (pin "40") (pinfunction "40_40") (pintype "passive"))
    )
    (net (code "64") (name "unconnected-(U$4-VPP-Pad5)") (class "Default")
      (node (ref "U$4") (pin "5") (pinfunction "VPP_5") (pintype "bidirectional"))
    )
    (net (code "65") (name "unconnected-(U$5-ADC-PadP$50)") (class "Default")
      (node (ref "U$5") (pin "P$50") (pinfunction "ADC_P$50") (pintype "bidirectional"))
    )
    (net (code "66") (name "unconnected-(U$5-BPI_BUS1-PadP$5)") (class "Default")
      (node (ref "U$5") (pin "P$5") (pinfunction "BPI_BUS1_P$5") (pintype "bidirectional"))
    )
    (net (code "67") (name "unconnected-(U$5-BT_ANT-PadP$36)") (class "Default")
      (node (ref "U$5") (pin "P$36") (pinfunction "BT_ANT_P$36") (pintype "bidirectional"))
    )
    (net (code "68") (name "unconnected-(U$5-COL0-PadP$20)") (class "Default")
      (node (ref "U$5") (pin "P$20") (pinfunction "COL0_P$20") (pintype "bidirectional"))
    )
    (net (code "69") (name "unconnected-(U$5-COL1-PadP$25)") (class "Default")
      (node (ref "U$5") (pin "P$25") (pinfunction "COL1_P$25") (pintype "bidirectional"))
    )
    (net (code "70") (name "unconnected-(U$5-COL2-PadP$22)") (class "Default")
      (node (ref "U$5") (pin "P$22") (pinfunction "COL2_P$22") (pintype "bidirectional"))
    )
    (net (code "71") (name "unconnected-(U$5-COL3-PadP$21)") (class "Default")
      (node (ref "U$5") (pin "P$21") (pinfunction "COL3_P$21") (pintype "bidirectional"))
    )
    (net (code "72") (name "unconnected-(U$5-COL4-PadP$24)") (class "Default")
      (node (ref "U$5") (pin "P$24") (pinfunction "COL4_P$24") (pintype "bidirectional"))
    )
    (net (code "73") (name "unconnected-(U$5-CTS-PadP$34)") (class "Default")
      (node (ref "U$5") (pin "P$34") (pinfunction "CTS_P$34") (pintype "bidirectional"))
    )
    (net (code "74") (name "unconnected-(U$5-FM_ANT_N-PadP$57)") (class "Default")
      (node (ref "U$5") (pin "P$57") (pinfunction "FM_ANT_N_P$57") (pintype "bidirectional"))
    )
    (net (code "75") (name "unconnected-(U$5-FM_ANT_P-PadP$17)") (class "Default")
      (node (ref "U$5") (pin "P$17") (pinfunction "FM_ANT_P_P$17") (pintype "bidirectional"))
    )
    (net (code "76") (name "unconnected-(U$5-GPIO1-PadP$3)") (class "Default")
      (node (ref "U$5") (pin "P$3") (pinfunction "GPIO1_P$3") (pintype "bidirectional"))
    )
    (net (code "77") (name "unconnected-(U$5-GPIO2-PadP$27)") (class "Default")
      (node (ref "U$5") (pin "P$27") (pinfunction "GPIO2_P$27") (pintype "bidirectional"))
    )
    (net (code "78") (name "unconnected-(U$5-GPIO3-PadP$28)") (class "Default")
      (node (ref "U$5") (pin "P$28") (pinfunction "GPIO3_P$28") (pintype "bidirectional"))
    )
    (net (code "79") (name "unconnected-(U$5-ISINK0-PadP$47)") (class "Default")
      (node (ref "U$5") (pin "P$47") (pinfunction "ISINK0_P$47") (pintype "bidirectional"))
    )
    (net (code "80") (name "unconnected-(U$5-ISINK1-PadP$46)") (class "Default")
      (node (ref "U$5") (pin "P$46") (pinfunction "ISINK1_P$46") (pintype "bidirectional"))
    )
    (net (code "81") (name "unconnected-(U$5-MIC1N-PadP$12)") (class "Default")
      (node (ref "U$5") (pin "P$12") (pinfunction "MIC1N_P$12") (pintype "bidirectional"))
    )
    (net (code "82") (name "unconnected-(U$5-MIC1P-PadP$52)") (class "Default")
      (node (ref "U$5") (pin "P$52") (pinfunction "MIC1P_P$52") (pintype "bidirectional"))
    )
    (net (code "83") (name "unconnected-(U$5-MIC2N-PadP$10)") (class "Default")
      (node (ref "U$5") (pin "P$10") (pinfunction "MIC2N_P$10") (pintype "bidirectional"))
    )
    (net (code "84") (name "unconnected-(U$5-MIC2P-PadP$9)") (class "Default")
      (node (ref "U$5") (pin "P$9") (pinfunction "MIC2P_P$9") (pintype "bidirectional"))
    )
    (net (code "85") (name "unconnected-(U$5-NETLIGHT-PadP$64)") (class "Default")
      (node (ref "U$5") (pin "P$64") (pinfunction "NETLIGHT_P$64") (pintype "bidirectional"))
    )
    (net (code "86") (name "unconnected-(U$5-PCMCLK-PadP$29)") (class "Default")
      (node (ref "U$5") (pin "P$29") (pinfunction "PCMCLK_P$29") (pintype "bidirectional"))
    )
    (net (code "87") (name "unconnected-(U$5-PCMIN-PadP$66)") (class "Default")
      (node (ref "U$5") (pin "P$66") (pinfunction "PCMIN_P$66") (pintype "bidirectional"))
    )
    (net (code "88") (name "unconnected-(U$5-PCMOUT-PadP$30)") (class "Default")
      (node (ref "U$5") (pin "P$30") (pinfunction "PCMOUT_P$30") (pintype "bidirectional"))
    )
    (net (code "89") (name "unconnected-(U$5-PCMSYNC-PadP$65)") (class "Default")
      (node (ref "U$5") (pin "P$65") (pinfunction "PCMSYNC_P$65") (pintype "bidirectional"))
    )
    (net (code "90") (name "unconnected-(U$5-PWM-PadP$26)") (class "Default")
      (node (ref "U$5") (pin "P$26") (pinfunction "PWM_P$26") (pintype "bidirectional"))
    )
    (net (code "91") (name "unconnected-(U$5-PWRKEY-PadP$48)") (class "Default")
      (node (ref "U$5") (pin "P$48") (pinfunction "PWRKEY_P$48") (pintype "bidirectional"))
    )
    (net (code "92") (name "unconnected-(U$5-RESET-PadP$49)") (class "Default")
      (node (ref "U$5") (pin "P$49") (pinfunction "RESET_P$49") (pintype "bidirectional"))
    )
    (net (code "93") (name "unconnected-(U$5-ROW0-PadP$62)") (class "Default")
      (node (ref "U$5") (pin "P$62") (pinfunction "ROW0_P$62") (pintype "bidirectional"))
    )
    (net (code "94") (name "unconnected-(U$5-ROW1-PadP$60)") (class "Default")
      (node (ref "U$5") (pin "P$60") (pinfunction "ROW1_P$60") (pintype "bidirectional"))
    )
    (net (code "95") (name "unconnected-(U$5-ROW2-PadP$61)") (class "Default")
      (node (ref "U$5") (pin "P$61") (pinfunction "ROW2_P$61") (pintype "bidirectional"))
    )
    (net (code "96") (name "unconnected-(U$5-ROW3-PadP$23)") (class "Default")
      (node (ref "U$5") (pin "P$23") (pinfunction "ROW3_P$23") (pintype "bidirectional"))
    )
    (net (code "97") (name "unconnected-(U$5-ROW4-PadP$63)") (class "Default")
      (node (ref "U$5") (pin "P$63") (pinfunction "ROW4_P$63") (pintype "bidirectional"))
    )
    (net (code "98") (name "unconnected-(U$5-RTS-PadP$33)") (class "Default")
      (node (ref "U$5") (pin "P$33") (pinfunction "RTS_P$33") (pintype "bidirectional"))
    )
    (net (code "99") (name "unconnected-(U$5-SCL-PadP$74)") (class "Default")
      (node (ref "U$5") (pin "P$74") (pinfunction "SCL_P$74") (pintype "bidirectional"))
    )
    (net (code "100") (name "unconnected-(U$5-SDA-PadP$75)") (class "Default")
      (node (ref "U$5") (pin "P$75") (pinfunction "SDA_P$75") (pintype "bidirectional"))
    )
    (net (code "101") (name "unconnected-(U$5-SIMPRE-PadP$54)") (class "Default")
      (node (ref "U$5") (pin "P$54") (pinfunction "SIMPRE_P$54") (pintype "bidirectional"))
    )
    (net (code "102") (name "unconnected-(U$5-SPK1N-PadP$13)") (class "Default")
      (node (ref "U$5") (pin "P$13") (pinfunction "SPK1N_P$13") (pintype "bidirectional"))
    )
    (net (code "103") (name "unconnected-(U$5-SPK1P-PadP$53)") (class "Default")
      (node (ref "U$5") (pin "P$53") (pinfunction "SPK1P_P$53") (pintype "bidirectional"))
    )
    (net (code "104") (name "unconnected-(U$5-SPK2N-PadP$11)") (class "Default")
      (node (ref "U$5") (pin "P$11") (pinfunction "SPK2N_P$11") (pintype "bidirectional"))
    )
    (net (code "105") (name "unconnected-(U$5-SPL2P-PadP$51)") (class "Default")
      (node (ref "U$5") (pin "P$51") (pinfunction "SPL2P_P$51") (pintype "bidirectional"))
    )
    (net (code "106") (name "unconnected-(U$5-STATUS-PadP$4)") (class "Default")
      (node (ref "U$5") (pin "P$4") (pinfunction "STATUS_P$4") (pintype "bidirectional"))
    )
    (net (code "107") (name "unconnected-(U$5-UART_DCD-PadP$70)") (class "Default")
      (node (ref "U$5") (pin "P$70") (pinfunction "UART_DCD_P$70") (pintype "bidirectional"))
    )
    (net (code "108") (name "unconnected-(U$5-UART_DRT-PadP$69)") (class "Default")
      (node (ref "U$5") (pin "P$69") (pinfunction "UART_DRT_P$69") (pintype "bidirectional"))
    )
    (net (code "109") (name "unconnected-(U$5-UART_RI-PadP$68)") (class "Default")
      (node (ref "U$5") (pin "P$68") (pinfunction "UART_RI_P$68") (pintype "bidirectional"))
    )
    (net (code "110") (name "unconnected-(U$5-USB_DM-PadP$19)") (class "Default")
      (node (ref "U$5") (pin "P$19") (pinfunction "USB_DM_P$19") (pintype "bidirectional"))
    )
    (net (code "111") (name "unconnected-(U$5-USB_DP-PadP$59)") (class "Default")
      (node (ref "U$5") (pin "P$59") (pinfunction "USB_DP_P$59") (pintype "bidirectional"))
    )
    (net (code "112") (name "unconnected-(U$5-VBUS-PadP$7)") (class "Default")
      (node (ref "U$5") (pin "P$7") (pinfunction "VBUS_P$7") (pintype "bidirectional"))
    )
    (net (code "113") (name "unconnected-(U2-DEN(G)-Pad10)") (class "Default")
      (node (ref "U2") (pin "10") (pinfunction "DEN(G)_10") (pintype "bidirectional"))
    )
    (net (code "114") (name "unconnected-(U2-DRDY(G)-Pad12)") (class "Default")
      (node (ref "U2") (pin "12") (pinfunction "DRDY(G)_12") (pintype "bidirectional"))
    )
    (net (code "115") (name "unconnected-(U2-INT(G)-Pad11)") (class "Default")
      (node (ref "U2") (pin "11") (pinfunction "INT(G)_11") (pintype "bidirectional"))
    )
    (net (code "116") (name "unconnected-(U2-INT1(XM)-Pad13)") (class "Default")
      (node (ref "U2") (pin "13") (pinfunction "INT1(XM)_13") (pintype "bidirectional"))
    )
    (net (code "117") (name "unconnected-(U2-INT2(XM)-Pad14)") (class "Default")
      (node (ref "U2") (pin "14") (pinfunction "INT2(XM)_14") (pintype "bidirectional"))
    )
    (net (code "118") (name "unconnected-(U3-1PPS-PadP$13)") (class "Default")
      (node (ref "U3") (pin "P$13") (pinfunction "1PPS_P$13") (pintype "bidirectional"))
    )
    (net (code "119") (name "unconnected-(U3-3D-FIX-PadP$5)") (class "Default")
      (node (ref "U3") (pin "P$5") (pinfunction "3D-FIX_P$5") (pintype "bidirectional"))
    )
    (net (code "120") (name "unconnected-(U3-NC-PadP$6)") (class "Default")
      (node (ref "U3") (pin "P$6") (pinfunction "NC_P$6") (pintype "bidirectional"))
    )
    (net (code "121") (name "unconnected-(U3-NC-PadP$7)") (class "Default")
      (node (ref "U3") (pin "P$7") (pinfunction "NC_P$7") (pintype "bidirectional"))
    )
    (net (code "122") (name "unconnected-(U3-NC-PadP$15)") (class "Default")
      (node (ref "U3") (pin "P$15") (pinfunction "NC_P$15") (pintype "bidirectional"))
    )
    (net (code "123") (name "unconnected-(U3-NC-PadP$16)") (class "Default")
      (node (ref "U3") (pin "P$16") (pinfunction "NC_P$16") (pintype "bidirectional"))
    )
    (net (code "124") (name "unconnected-(U3-NC-PadP$17)") (class "Default")
      (node (ref "U3") (pin "P$17") (pinfunction "NC_P$17") (pintype "bidirectional"))
    )
    (net (code "125") (name "unconnected-(U3-NC-PadP$18)") (class "Default")
      (node (ref "U3") (pin "P$18") (pinfunction "NC_P$18") (pintype "bidirectional"))
    )
    (net (code "126") (name "unconnected-(U3-NC-PadP$20)") (class "Default")
      (node (ref "U3") (pin "P$20") (pinfunction "NC_P$20") (pintype "bidirectional"))
    )
    (net (code "127") (name "unconnected-(U3-NRESET-PadP$2)") (class "Default")
      (node (ref "U3") (pin "P$2") (pinfunction "NRESET_P$2") (pintype "bidirectional"))
    )
    (net (code "128") (name "unconnected-(U3-RTCM-PadP$14)") (class "Default")
      (node (ref "U3") (pin "P$14") (pinfunction "RTCM_P$14") (pintype "bidirectional"))
    )
    (net (code "129") (name "unconnected-(U3-VBACKUP-PadP$4)") (class "Default")
      (node (ref "U3") (pin "P$4") (pinfunction "VBACKUP_P$4") (pintype "bidirectional"))
    )
    (net (code "130") (name "unconnected-(U4-ALERT-Pad2)") (class "Default")
      (node (ref "U4") (pin "2") (pinfunction "ALERT_2") (pintype "bidirectional"))
    )
    (net (code "131") (name "unconnected-(U7A-CSSPIN{slash}PB_2A...-Pad8)") (class "Default")
      (node (ref "U7") (pin "8") (pinfunction "CSSPIN/PB_2A..._8") (pintype "bidirectional"))
    )
    (net (code "132") (name "unconnected-(U7A-DONE{slash}PT17D-Pad23)") (class "Default")
      (node (ref "U7") (pin "23") (pinfunction "DONE/PT17D_23") (pintype "bidirectional"))
    )
    (net (code "133") (name "unconnected-(U7A-INITN{slash}PT17C-PadNC1)") (class "Default")
      (node (ref "U7") (pin "NC1") (pinfunction "INITN/PT17C_NC1") (pintype "bidirectional"))
    )
    (net (code "134") (name "unconnected-(U7A-JTAGENB{slash}PT15C-Pad26)") (class "Default")
      (node (ref "U7") (pin "26") (pinfunction "JTAGENB/PT15C_26") (pintype "bidirectional"))
    )
    (net (code "135") (name "unconnected-(U7A-MCLK{slash}CCLK{slash}PB6C-Pad9)") (class "Default")
      (node (ref "U7") (pin "9") (pinfunction "MCLK/CCLK/PB6C_9") (pintype "bidirectional"))
    )
    (net (code "136") (name "unconnected-(U7A-PB_2B{slash}4B{slash}4D{slash}5B{slash}4B-PadNC2)") (class "Default")
      (node (ref "U7") (pin "NC2") (pinfunction "PB_2B/4B/4D/5B/4B_NC2") (pintype "bidirectional"))
    )
    (net (code "137") (name "unconnected-(U7A-SN{slash}PB20C-Pad16)") (class "Default")
      (node (ref "U7") (pin "16") (pinfunction "SN/PB20C_16") (pintype "bidirectional"))
    )
    (net (code "138") (name "unconnected-(U7A-SPISO{slash}PB6D-Pad10)") (class "Default")
      (node (ref "U7") (pin "10") (pinfunction "SPISO/PB6D_10") (pintype "bidirectional"))
    )
    (net (code "139") (name "unconnected-(U7A-TCK-Pad30)") (class "Default")
      (node (ref "U7") (pin "30") (pinfunction "TCK_30") (pintype "bidirectional"))
    )
    (net (code "140") (name "unconnected-(U7A-TDI-Pad32)") (class "Default")
      (node (ref "U7") (pin "32") (pinfunction "TDI_32") (pintype "bidirectional"))
    )
    (net (code "141") (name "unconnected-(U7A-TDO-Pad1)") (class "Default")
      (node (ref "U7") (pin "1") (pinfunction "TDO_1") (pintype "bidirectional"))
    )
    (net (code "142") (name "unconnected-(U7A-TMS-Pad29)") (class "Default")
      (node (ref "U7") (pin "29") (pinfunction "TMS_29") (pintype "bidirectional"))
    )
    (net (code "143") (name "unconnected-(U7B-PB_4A{slash}6C{slash}9A{slash}11A{slash}13A-Pad11)") (class "Default")
      (node (ref "U7") (pin "11") (pinfunction "PB_4A/6C/9A/11A/13A_11") (pintype "bidirectional"))
    )
    (net (code "144") (name "unconnected-(U7B-PB_4B{slash}6D{slash}9B{slash}11B{slash}13B-Pad12)") (class "Default")
      (node (ref "U7") (pin "12") (pinfunction "PB_4B/6D/9B/11B/13B_12") (pintype "bidirectional"))
    )
  )
)
